# Slave_Sheet1.net
KiCad netlist of a schematic drawn in Altium Designer
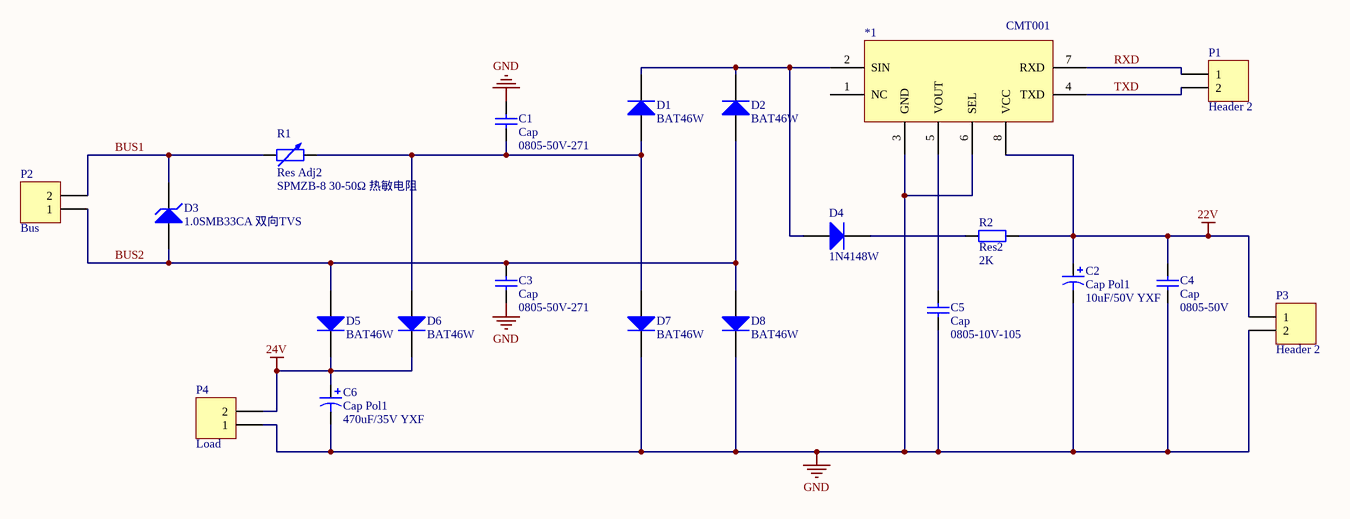
[diagram p0: Slave_Sheet1.SchDoc]

(export (version "E")
  (design (tool "Eeschema 10.0.6"))
  (components
    (comp (ref "*1")
      (value "CMT001")
      (footprint "MSOP-MS8_M")
      (description "从机")
      (libsource (lib "fszhang") (part "CMT001"))
    )
    (comp (ref "C1")
      (value "Cap")
      (footprint "0805-1")
      (description "Capacitor")
      (fields (field (name "ALTIUM_VALUE") "0805-50V-271") (field (name "PUBLISHER") "Altium Limited"))
      (libsource (lib "Miscellaneous Devices") (part "Cap"))
    )
    (comp (ref "C2")
      (value "Cap Pol1")
      (footprint "C-RB-8")
      (description "Polarized Capacitor (Radial)")
      (fields (field (name "ALTIUM_VALUE") "10uF/50V YXF") (field (name "PUBLISHER") "Altium Limited"))
      (libsource (lib "Miscellaneous Devices") (part "Cap Pol1"))
    )
    (comp (ref "C3")
      (value "Cap")
      (footprint "0805-1")
      (description "Capacitor")
      (fields (field (name "ALTIUM_VALUE") "0805-50V-271") (field (name "PUBLISHER") "Altium Limited"))
      (libsource (lib "Miscellaneous Devices") (part "Cap"))
    )
    (comp (ref "C4")
      (value "Cap")
      (footprint "0805-1")
      (description "Capacitor")
      (fields (field (name "ALTIUM_VALUE") "0805-50V") (field (name "PUBLISHER") "Altium Limited"))
      (libsource (lib "Miscellaneous Devices") (part "Cap"))
    )
    (comp (ref "C5")
      (value "Cap")
      (footprint "0805-1")
      (description "Capacitor")
      (fields (field (name "ALTIUM_VALUE") "0805-10V-105") (field (name "PUBLISHER") "Altium Limited"))
      (libsource (lib "Miscellaneous Devices") (part "Cap"))
    )
    (comp (ref "C6")
      (value "Cap Pol1")
      (footprint "C-RB-12")
      (description "Polarized Capacitor (Radial)")
      (fields (field (name "ALTIUM_VALUE") "470uF/35V YXF") (field (name "PUBLISHER") "Altium Limited"))
      (libsource (lib "Miscellaneous Devices") (part "Cap Pol1"))
    )
    (comp (ref "D1")
      (value "BAT46W")
      (footprint "SOD-123")
      (description "Default Diode")
      (fields (field (name "PUBLISHER") "Altium Limited"))
      (libsource (lib "Miscellaneous Devices") (part "Diode"))
    )
    (comp (ref "D2")
      (value "BAT46W")
      (footprint "SOD-123")
      (description "Default Diode")
      (fields (field (name "PUBLISHER") "Altium Limited"))
      (libsource (lib "Miscellaneous Devices") (part "Diode"))
    )
    (comp (ref "D3")
      (value "1.0SMB33CA 双向TVS")
      (footprint "DIODE-SMB")
      (description "Zener Diode")
      (fields (field (name "PUBLISHER") "Altium Limited"))
      (libsource (lib "Miscellaneous Devices") (part "D Zener"))
    )
    (comp (ref "D4")
      (value "1N4148W")
      (footprint "DO35")
      (description "Default Diode")
      (fields (field (name "PUBLISHER") "Altium Limited"))
      (libsource (lib "Miscellaneous Devices") (part "Diode"))
    )
    (comp (ref "D5")
      (value "BAT46W")
      (footprint "SOD-123")
      (description "Default Diode")
      (fields (field (name "PUBLISHER") "Altium Limited"))
      (libsource (lib "Miscellaneous Devices") (part "Diode"))
    )
    (comp (ref "D6")
      (value "BAT46W")
      (footprint "SOD-123")
      (description "Default Diode")
      (fields (field (name "PUBLISHER") "Altium Limited"))
      (libsource (lib "Miscellaneous Devices") (part "Diode"))
    )
    (comp (ref "D7")
      (value "BAT46W")
      (footprint "SOD-123")
      (description "Default Diode")
      (fields (field (name "PUBLISHER") "Altium Limited"))
      (libsource (lib "Miscellaneous Devices") (part "Diode"))
    )
    (comp (ref "D8")
      (value "BAT46W")
      (footprint "SOD-123")
      (description "Default Diode")
      (fields (field (name "PUBLISHER") "Altium Limited"))
      (libsource (lib "Miscellaneous Devices") (part "Diode"))
    )
    (comp (ref "P1")
      (value "Header 2")
      (footprint "HDR1X2")
      (description "Header, 2-Pin")
      (fields (field (name "PUBLISHER") "Altium Limited"))
      (libsource (lib "") (part "Header 2_1"))
    )
    (comp (ref "P2")
      (value "Bus")
      (footprint "HDR1X2")
      (description "Header, 2-Pin")
      (fields (field (name "PUBLISHER") "Altium Limited"))
      (libsource (lib "Miscellaneous Connectors") (part "Header 2"))
    )
    (comp (ref "P3")
      (value "Header 2")
      (footprint "HDR1X2")
      (description "Header, 2-Pin")
      (fields (field (name "PUBLISHER") "Altium Limited"))
      (libsource (lib "") (part "Header 2_1"))
    )
    (comp (ref "P4")
      (value "Load")
      (footprint "HDR1X2")
      (description "Header, 2-Pin")
      (fields (field (name "PUBLISHER") "Altium Limited"))
      (libsource (lib "Miscellaneous Connectors") (part "Header 2"))
    )
    (comp (ref "R1")
      (value "Res Adj2")
      (footprint "AXIAL-0.6")
      (description "Variable Resistor")
      (fields (field (name "ALTIUM_VALUE") "SPMZB-8 30-50Ω 热敏电阻") (field (name "PUBLISHER") "Altium Limited"))
      (libsource (lib "Miscellaneous Devices") (part "Res Adj2"))
    )
    (comp (ref "R2")
      (value "Res2")
      (footprint "0805-1")
      (description "Resistor")
      (fields (field (name "ALTIUM_VALUE") "2K") (field (name "PUBLISHER") "Altium Limited"))
      (libsource (lib "Miscellaneous Devices") (part "Res2"))
    )
  )
  (nets
    (net (code "1") (name "/BUS1") (class "Default")
      (node (ref "D3") (pin "2") (pinfunction "K_2") (pintype "passive"))
      (node (ref "P2") (pin "2") (pinfunction "2_2") (pintype "passive"))
      (node (ref "R1") (pin "1") (pinfunction "1_1") (pintype "passive"))
    )
    (net (code "2") (name "/BUS2") (class "Default")
      (node (ref "C3") (pin "2") (pinfunction "2_2") (pintype "passive"))
      (node (ref "D2") (pin "1") (pinfunction "A_1") (pintype "passive"))
      (node (ref "D3") (pin "1") (pinfunction "A_1") (pintype "passive"))
      (node (ref "D5") (pin "1") (pinfunction "A_1") (pintype "passive"))
      (node (ref "D8") (pin "1") (pinfunction "A_1") (pintype "passive"))
      (node (ref "P2") (pin "1") (pinfunction "1_1") (pintype "passive"))
    )
    (net (code "3") (name "/RXD") (class "Default")
      (node (ref "*1") (pin "7") (pinfunction "RXD_7") (pintype "passive"))
      (node (ref "P1") (pin "1") (pinfunction "1_1") (pintype "passive"))
    )
    (net (code "4") (name "/TXD") (class "Default")
      (node (ref "*1") (pin "4") (pinfunction "TXD_4") (pintype "passive"))
      (node (ref "P1") (pin "2") (pinfunction "2_2") (pintype "passive"))
    )
    (net (code "5") (name "22V") (class "Default")
      (node (ref "*1") (pin "8") (pinfunction "VCC_8") (pintype "passive"))
      (node (ref "C2") (pin "1") (pinfunction "1_1") (pintype "passive"))
      (node (ref "C4") (pin "2") (pinfunction "2_2") (pintype "passive"))
      (node (ref "P3") (pin "1") (pinfunction "1_1") (pintype "passive"))
      (node (ref "R2") (pin "2") (pinfunction "2_2") (pintype "passive"))
    )
    (net (code "6") (name "24V") (class "Default")
      (node (ref "C6") (pin "1") (pinfunction "1_1") (pintype "passive"))
      (node (ref "D5") (pin "2") (pinfunction "K_2") (pintype "passive"))
      (node (ref "D6") (pin "2") (pinfunction "K_2") (pintype "passive"))
      (node (ref "P4") (pin "2") (pinfunction "2_2") (pintype "passive"))
    )
    (net (code "7") (name "GND") (class "Default")
      (node (ref "*1") (pin "3") (pinfunction "GND_3") (pintype "passive"))
      (node (ref "*1") (pin "6") (pinfunction "SEL_6") (pintype "passive"))
      (node (ref "C1") (pin "2") (pinfunction "2_2") (pintype "passive"))
      (node (ref "C2") (pin "2") (pinfunction "2_2") (pintype "passive"))
      (node (ref "C3") (pin "1") (pinfunction "1_1") (pintype "passive"))
      (node (ref "C4") (pin "1") (pinfunction "1_1") (pintype "passive"))
      (node (ref "C5") (pin "1") (pinfunction "1_1") (pintype "passive"))
      (node (ref "C6") (pin "2") (pinfunction "2_2") (pintype "passive"))
      (node (ref "D7") (pin "2") (pinfunction "K_2") (pintype "passive"))
      (node (ref "D8") (pin "2") (pinfunction "K_2") (pintype "passive"))
      (node (ref "P3") (pin "2") (pinfunction "2_2") (pintype "passive"))
      (node (ref "P4") (pin "1") (pinfunction "1_1") (pintype "passive"))
    )
    (net (code "8") (name "Net-(*1-SIN)") (class "Default")
      (node (ref "*1") (pin "2") (pinfunction "SIN_2") (pintype "passive"))
      (node (ref "D1") (pin "2") (pinfunction "K_2") (pintype "passive"))
      (node (ref "D2") (pin "2") (pinfunction "K_2") (pintype "passive"))
      (node (ref "D4") (pin "1") (pinfunction "A_1") (pintype "passive"))
    )
    (net (code "9") (name "Net-(*1-VOUT)") (class "Default")
      (node (ref "*1") (pin "5") (pinfunction "VOUT_5") (pintype "passive"))
      (node (ref "C5") (pin "2") (pinfunction "2_2") (pintype "passive"))
    )
    (net (code "10") (name "Net-(D1-A)") (class "Default")
      (node (ref "C1") (pin "1") (pinfunction "1_1") (pintype "passive"))
      (node (ref "D1") (pin "1") (pinfunction "A_1") (pintype "passive"))
      (node (ref "D6") (pin "1") (pinfunction "A_1") (pintype "passive"))
      (node (ref "D7") (pin "1") (pinfunction "A_1") (pintype "passive"))
      (node (ref "R1") (pin "2") (pinfunction "2_2") (pintype "passive"))
    )
    (net (code "11") (name "Net-(D4-K)") (class "Default")
      (node (ref "D4") (pin "2") (pinfunction "K_2") (pintype "passive"))
      (node (ref "R2") (pin "1") (pinfunction "1_1") (pintype "passive"))
    )
    (net (code "12") (name "unconnected-(*1-NC-Pad1)") (class "Default")
      (node (ref "*1") (pin "1") (pinfunction "NC_1") (pintype "passive"))
    )
  )
)
